# 2332_adapter_PET.net
KiCad netlist of a schematic drawn in EAGLE
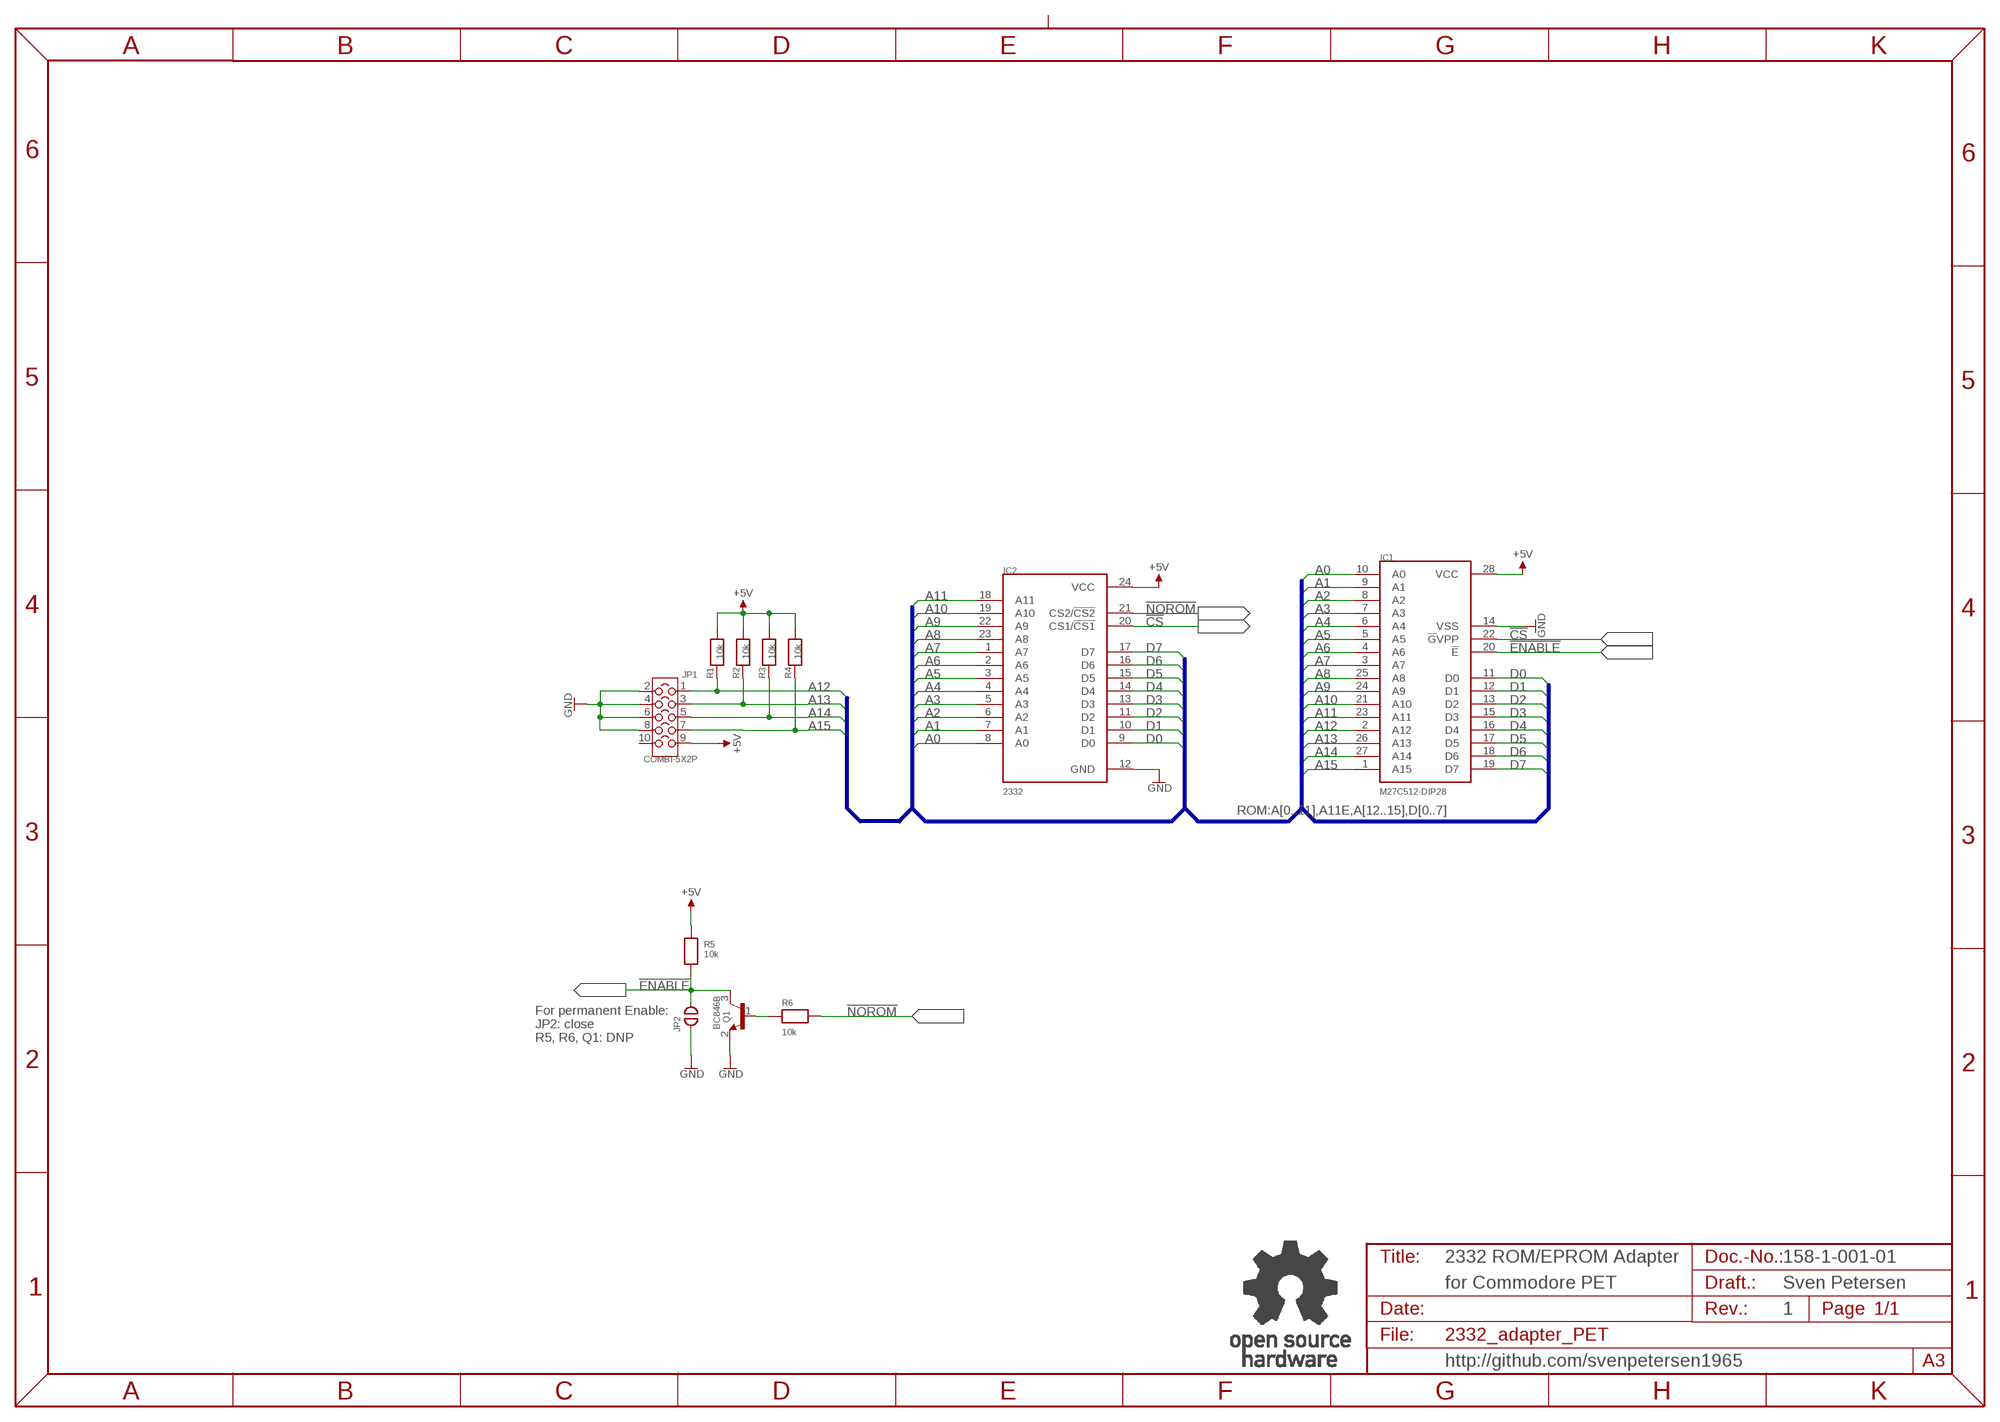
[diagram p0: schematic, sheet 1]

(export (version "E")
  (design (tool "Eeschema 10.0.6"))
  (components
    (comp (ref "IC1")
      (value "M27C512-DIP28")
      (footprint "eagle-import:DIL28-6")
      (libsource (lib "eagle-import") (part "M27C512-DIP28"))
    )
    (comp (ref "IC2")
      (value "2332")
      (footprint "eagle-import:DIL24_SOCKET")
      (libsource (lib "eagle-import") (part "2332"))
    )
    (comp (ref "JP1")
      (value "COMBI-5X2P")
      (footprint "eagle-import:COMBI-5X2")
      (libsource (lib "eagle-import") (part "COMBI-5X2P"))
    )
    (comp (ref "JP2")
      (value "OPEN")
      (footprint "eagle-import:CP_OP")
      (libsource (lib "eagle-import") (part "OPEN"))
    )
    (comp (ref "Q1")
      (value "BC846B")
      (footprint "eagle-import:SOT23")
      (libsource (lib "eagle-import") (part "BC846"))
    )
    (comp (ref "R1")
      (value "10k")
      (footprint "eagle-import:0805")
      (libsource (lib "eagle-import") (part "R-0805"))
    )
    (comp (ref "R2")
      (value "10k")
      (footprint "eagle-import:0805")
      (libsource (lib "eagle-import") (part "R-0805"))
    )
    (comp (ref "R3")
      (value "10k")
      (footprint "eagle-import:0805")
      (libsource (lib "eagle-import") (part "R-0805"))
    )
    (comp (ref "R4")
      (value "10k")
      (footprint "eagle-import:0805")
      (libsource (lib "eagle-import") (part "R-0805"))
    )
    (comp (ref "R5")
      (value "10k")
      (footprint "eagle-import:0805")
      (libsource (lib "eagle-import") (part "R-0805"))
    )
    (comp (ref "R6")
      (value "10k")
      (footprint "eagle-import:0805")
      (libsource (lib "eagle-import") (part "R-0805"))
    )
    (comp (ref "U$6")
      (value "OPEN_SOURCE_HW")
      (footprint "eagle-import:OPENHW")
      (libsource (lib "eagle-import") (part "OPEN_SOURCE_HW"))
    )
  )
  (nets
    (net (code "2") (name "+5V") (class "Default")
      (node (ref "IC1") (pin "28") (pinfunction "VCC_28") (pintype "power_in"))
      (node (ref "IC2") (pin "24") (pinfunction "VCC_24") (pintype "power_in"))
      (node (ref "JP1") (pin "9") (pinfunction "9_9") (pintype "bidirectional"))
      (node (ref "R1") (pin "2") (pinfunction "2_2") (pintype "passive"))
      (node (ref "R2") (pin "2") (pinfunction "2_2") (pintype "passive"))
      (node (ref "R3") (pin "2") (pinfunction "2_2") (pintype "passive"))
      (node (ref "R4") (pin "2") (pinfunction "2_2") (pintype "passive"))
      (node (ref "R5") (pin "2") (pinfunction "2_2") (pintype "passive"))
    )
    (net (code "3") (name "/A0") (class "Default")
      (node (ref "IC1") (pin "10") (pinfunction "A0_10") (pintype "input"))
      (node (ref "IC2") (pin "8") (pinfunction "A0_8") (pintype "input"))
    )
    (net (code "4") (name "/A1") (class "Default")
      (node (ref "IC1") (pin "9") (pinfunction "A1_9") (pintype "input"))
      (node (ref "IC2") (pin "7") (pinfunction "A1_7") (pintype "input"))
    )
    (net (code "5") (name "/A2") (class "Default")
      (node (ref "IC1") (pin "8") (pinfunction "A2_8") (pintype "input"))
      (node (ref "IC2") (pin "6") (pinfunction "A2_6") (pintype "input"))
    )
    (net (code "6") (name "/A3") (class "Default")
      (node (ref "IC1") (pin "7") (pinfunction "A3_7") (pintype "input"))
      (node (ref "IC2") (pin "5") (pinfunction "A3_5") (pintype "input"))
    )
    (net (code "7") (name "/A4") (class "Default")
      (node (ref "IC1") (pin "6") (pinfunction "A4_6") (pintype "input"))
      (node (ref "IC2") (pin "4") (pinfunction "A4_4") (pintype "input"))
    )
    (net (code "8") (name "/A5") (class "Default")
      (node (ref "IC1") (pin "5") (pinfunction "A5_5") (pintype "input"))
      (node (ref "IC2") (pin "3") (pinfunction "A5_3") (pintype "input"))
    )
    (net (code "9") (name "/A6") (class "Default")
      (node (ref "IC1") (pin "4") (pinfunction "A6_4") (pintype "input"))
      (node (ref "IC2") (pin "2") (pinfunction "A6_2") (pintype "input"))
    )
    (net (code "10") (name "/A7") (class "Default")
      (node (ref "IC1") (pin "3") (pinfunction "A7_3") (pintype "input"))
      (node (ref "IC2") (pin "1") (pinfunction "A7_1") (pintype "input"))
    )
    (net (code "11") (name "/A8") (class "Default")
      (node (ref "IC1") (pin "25") (pinfunction "A8_25") (pintype "input"))
      (node (ref "IC2") (pin "23") (pinfunction "A8_23") (pintype "input"))
    )
    (net (code "12") (name "/A9") (class "Default")
      (node (ref "IC1") (pin "24") (pinfunction "A9_24") (pintype "input"))
      (node (ref "IC2") (pin "22") (pinfunction "A9_22") (pintype "input"))
    )
    (net (code "13") (name "/A10") (class "Default")
      (node (ref "IC1") (pin "21") (pinfunction "A10_21") (pintype "input"))
      (node (ref "IC2") (pin "19") (pinfunction "A10_19") (pintype "input"))
    )
    (net (code "14") (name "/A11") (class "Default")
      (node (ref "IC1") (pin "23") (pinfunction "A11_23") (pintype "input"))
      (node (ref "IC2") (pin "18") (pinfunction "A11_18") (pintype "input"))
    )
    (net (code "15") (name "/A12") (class "Default")
      (node (ref "IC1") (pin "2") (pinfunction "A12_2") (pintype "input"))
      (node (ref "JP1") (pin "1") (pinfunction "1_1") (pintype "bidirectional"))
      (node (ref "R1") (pin "1") (pinfunction "1_1") (pintype "passive"))
    )
    (net (code "16") (name "/A13") (class "Default")
      (node (ref "IC1") (pin "26") (pinfunction "A13_26") (pintype "input"))
      (node (ref "JP1") (pin "3") (pinfunction "3_3") (pintype "bidirectional"))
      (node (ref "R2") (pin "1") (pinfunction "1_1") (pintype "passive"))
    )
    (net (code "17") (name "/A14") (class "Default")
      (node (ref "IC1") (pin "27") (pinfunction "A14_27") (pintype "input"))
      (node (ref "JP1") (pin "5") (pinfunction "5_5") (pintype "bidirectional"))
      (node (ref "R3") (pin "1") (pinfunction "1_1") (pintype "passive"))
    )
    (net (code "18") (name "/A15") (class "Default")
      (node (ref "IC1") (pin "1") (pinfunction "A15_1") (pintype "input"))
      (node (ref "JP1") (pin "7") (pinfunction "7_7") (pintype "bidirectional"))
      (node (ref "R4") (pin "1") (pinfunction "1_1") (pintype "passive"))
    )
    (net (code "19") (name "/D0") (class "Default")
      (node (ref "IC1") (pin "11") (pinfunction "D0_11") (pintype "bidirectional"))
      (node (ref "IC2") (pin "9") (pinfunction "D0_9") (pintype "tri_state"))
    )
    (net (code "20") (name "/D1") (class "Default")
      (node (ref "IC1") (pin "12") (pinfunction "D1_12") (pintype "bidirectional"))
      (node (ref "IC2") (pin "10") (pinfunction "D1_10") (pintype "tri_state"))
    )
    (net (code "21") (name "/D2") (class "Default")
      (node (ref "IC1") (pin "13") (pinfunction "D2_13") (pintype "bidirectional"))
      (node (ref "IC2") (pin "11") (pinfunction "D2_11") (pintype "tri_state"))
    )
    (net (code "22") (name "/D3") (class "Default")
      (node (ref "IC1") (pin "15") (pinfunction "D3_15") (pintype "bidirectional"))
      (node (ref "IC2") (pin "13") (pinfunction "D3_13") (pintype "tri_state"))
    )
    (net (code "23") (name "/D4") (class "Default")
      (node (ref "IC1") (pin "16") (pinfunction "D4_16") (pintype "bidirectional"))
      (node (ref "IC2") (pin "14") (pinfunction "D4_14") (pintype "tri_state"))
    )
    (net (code "24") (name "/D5") (class "Default")
      (node (ref "IC1") (pin "17") (pinfunction "D5_17") (pintype "bidirectional"))
      (node (ref "IC2") (pin "15") (pinfunction "D5_15") (pintype "tri_state"))
    )
    (net (code "25") (name "/D6") (class "Default")
      (node (ref "IC1") (pin "18") (pinfunction "D6_18") (pintype "bidirectional"))
      (node (ref "IC2") (pin "16") (pinfunction "D6_16") (pintype "tri_state"))
    )
    (net (code "26") (name "/D7") (class "Default")
      (node (ref "IC1") (pin "19") (pinfunction "D7_19") (pintype "bidirectional"))
      (node (ref "IC2") (pin "17") (pinfunction "D7_17") (pintype "tri_state"))
    )
    (net (code "28") (name "/~{CS}") (class "Default")
      (node (ref "IC1") (pin "22") (pinfunction "~{G}VPP_22") (pintype "input"))
      (node (ref "IC2") (pin "20") (pinfunction "CS1/~{CS1}_20") (pintype "input"))
    )
    (net (code "29") (name "/~{ENABLE}") (class "Default")
      (node (ref "IC1") (pin "20") (pinfunction "~{E}_20") (pintype "input"))
      (node (ref "JP2") (pin "2") (pinfunction "2_2") (pintype "passive"))
      (node (ref "Q1") (pin "3") (pinfunction "C_3") (pintype "passive"))
      (node (ref "R5") (pin "1") (pinfunction "1_1") (pintype "passive"))
    )
    (net (code "30") (name "/~{NOROM}") (class "Default")
      (node (ref "IC2") (pin "21") (pinfunction "CS2/~{CS2}_21") (pintype "input"))
      (node (ref "R6") (pin "2") (pinfunction "2_2") (pintype "passive"))
    )
    (net (code "31") (name "GND") (class "Default")
      (node (ref "IC1") (pin "14") (pinfunction "VSS_14") (pintype "power_in"))
      (node (ref "IC2") (pin "12") (pinfunction "GND_12") (pintype "power_in"))
      (node (ref "JP1") (pin "2") (pinfunction "2_2") (pintype "bidirectional"))
      (node (ref "JP1") (pin "4") (pinfunction "4_4") (pintype "bidirectional"))
      (node (ref "JP1") (pin "6") (pinfunction "6_6") (pintype "bidirectional"))
      (node (ref "JP1") (pin "8") (pinfunction "8_8") (pintype "bidirectional"))
      (node (ref "JP2") (pin "1") (pinfunction "1_1") (pintype "passive"))
      (node (ref "Q1") (pin "2") (pinfunction "E_2") (pintype "passive"))
    )
    (net (code "32") (name "Net-(Q1-B)") (class "Default")
      (node (ref "Q1") (pin "1") (pinfunction "B_1") (pintype "passive"))
      (node (ref "R6") (pin "1") (pinfunction "1_1") (pintype "passive"))
    )
    (net (code "33") (name "unconnected-(JP1-Pad10)") (class "Default")
      (node (ref "JP1") (pin "10") (pinfunction "10_10") (pintype "bidirectional"))
    )
  )
)
